# ad9200_breakout.net
KiCad netlist of a schematic drawn in EAGLE
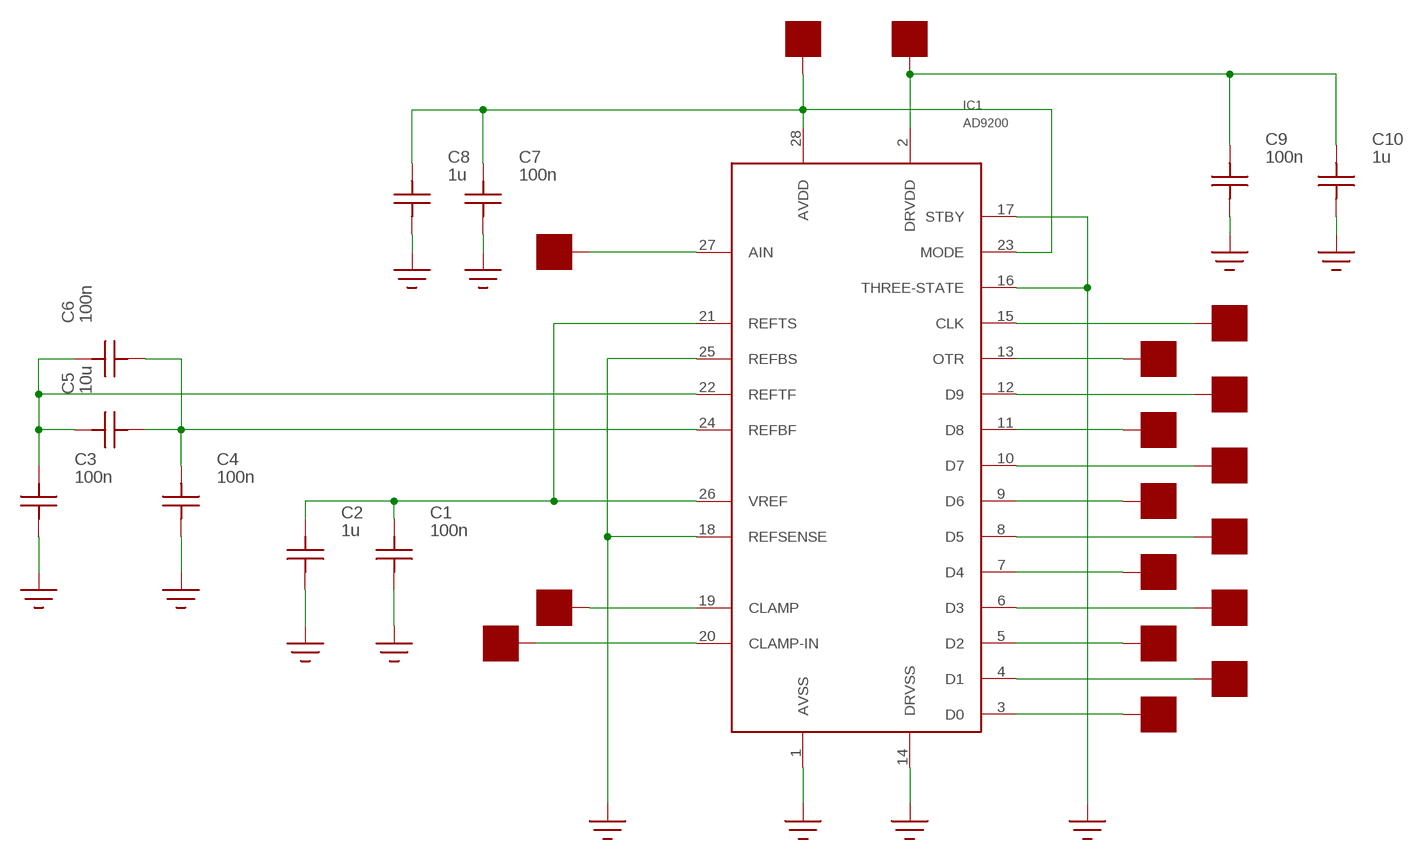
[diagram p0: schematic, sheet 1]

(export (version "E")
  (design (tool "Eeschema 10.0.6"))
  (components
    (comp (ref "C1")
      (value "100n")
      (footprint "eagle-import:C0603")
      (libsource (lib "eagle-import") (part "C0603"))
    )
    (comp (ref "C2")
      (value "1u")
      (footprint "eagle-import:C0603")
      (libsource (lib "eagle-import") (part "C0603"))
    )
    (comp (ref "C3")
      (value "100n")
      (footprint "eagle-import:C0603")
      (libsource (lib "eagle-import") (part "C0603"))
    )
    (comp (ref "C4")
      (value "100n")
      (footprint "eagle-import:C0603")
      (libsource (lib "eagle-import") (part "C0603"))
    )
    (comp (ref "C5")
      (value "10u")
      (footprint "eagle-import:C0603")
      (libsource (lib "eagle-import") (part "C0603"))
    )
    (comp (ref "C6")
      (value "100n")
      (footprint "eagle-import:C0603")
      (libsource (lib "eagle-import") (part "C0603"))
    )
    (comp (ref "C7")
      (value "100n")
      (footprint "eagle-import:C0603")
      (libsource (lib "eagle-import") (part "C0603"))
    )
    (comp (ref "C8")
      (value "1u")
      (footprint "eagle-import:C0603")
      (libsource (lib "eagle-import") (part "C0603"))
    )
    (comp (ref "C9")
      (value "100n")
      (footprint "eagle-import:C0603")
      (libsource (lib "eagle-import") (part "C0603"))
    )
    (comp (ref "C10")
      (value "1u")
      (footprint "eagle-import:C0603")
      (libsource (lib "eagle-import") (part "C0603"))
    )
    (comp (ref "IC1")
      (value "AD9200")
      (footprint "eagle-import:SSOP-28")
      (libsource (lib "eagle-import") (part "AD9200"))
    )
    (comp (ref "U$5")
      (value "PAD50MIL")
      (footprint "eagle-import:PAD_50MIL")
      (libsource (lib "eagle-import") (part "PAD50MIL"))
    )
    (comp (ref "U$6")
      (value "PAD50MIL")
      (footprint "eagle-import:PAD_50MIL")
      (libsource (lib "eagle-import") (part "PAD50MIL"))
    )
    (comp (ref "U$7")
      (value "PAD50MIL")
      (footprint "eagle-import:PAD_50MIL")
      (libsource (lib "eagle-import") (part "PAD50MIL"))
    )
    (comp (ref "U$8")
      (value "PAD50MIL")
      (footprint "eagle-import:PAD_50MIL")
      (libsource (lib "eagle-import") (part "PAD50MIL"))
    )
    (comp (ref "U$9")
      (value "PAD50MIL")
      (footprint "eagle-import:PAD_50MIL")
      (libsource (lib "eagle-import") (part "PAD50MIL"))
    )
    (comp (ref "U$10")
      (value "PAD50MIL")
      (footprint "eagle-import:PAD_50MIL")
      (libsource (lib "eagle-import") (part "PAD50MIL"))
    )
    (comp (ref "U$11")
      (value "PAD50MIL")
      (footprint "eagle-import:PAD_50MIL")
      (libsource (lib "eagle-import") (part "PAD50MIL"))
    )
    (comp (ref "U$12")
      (value "PAD50MIL")
      (footprint "eagle-import:PAD_50MIL")
      (libsource (lib "eagle-import") (part "PAD50MIL"))
    )
    (comp (ref "U$13")
      (value "PAD50MIL")
      (footprint "eagle-import:PAD_50MIL")
      (libsource (lib "eagle-import") (part "PAD50MIL"))
    )
    (comp (ref "U$14")
      (value "PAD50MIL")
      (footprint "eagle-import:PAD_50MIL")
      (libsource (lib "eagle-import") (part "PAD50MIL"))
    )
    (comp (ref "U$15")
      (value "PAD50MIL")
      (footprint "eagle-import:PAD_50MIL")
      (libsource (lib "eagle-import") (part "PAD50MIL"))
    )
    (comp (ref "U$16")
      (value "PAD50MIL")
      (footprint "eagle-import:PAD_50MIL")
      (libsource (lib "eagle-import") (part "PAD50MIL"))
    )
    (comp (ref "U$17")
      (value "PAD50MIL")
      (footprint "eagle-import:PAD_50MIL")
      (libsource (lib "eagle-import") (part "PAD50MIL"))
    )
    (comp (ref "U$18")
      (value "PAD50MIL")
      (footprint "eagle-import:PAD_50MIL")
      (libsource (lib "eagle-import") (part "PAD50MIL"))
    )
    (comp (ref "U$19")
      (value "PAD50MIL")
      (footprint "eagle-import:PAD_50MIL")
      (libsource (lib "eagle-import") (part "PAD50MIL"))
    )
    (comp (ref "U$20")
      (value "PAD50MIL")
      (footprint "eagle-import:PAD_50MIL")
      (libsource (lib "eagle-import") (part "PAD50MIL"))
    )
    (comp (ref "U$21")
      (value "PAD50MIL")
      (footprint "eagle-import:PAD_50MIL")
      (libsource (lib "eagle-import") (part "PAD50MIL"))
    )
  )
  (nets
    (net (code "1") (name "GND") (class "Default")
      (node (ref "C1") (pin "P$1") (pinfunction "P$1_P$1") (pintype "bidirectional"))
      (node (ref "C10") (pin "P$1") (pinfunction "P$1_P$1") (pintype "bidirectional"))
      (node (ref "C2") (pin "P$1") (pinfunction "P$1_P$1") (pintype "bidirectional"))
      (node (ref "C3") (pin "P$1") (pinfunction "P$1_P$1") (pintype "bidirectional"))
      (node (ref "C4") (pin "P$1") (pinfunction "P$1_P$1") (pintype "bidirectional"))
      (node (ref "C7") (pin "P$1") (pinfunction "P$1_P$1") (pintype "bidirectional"))
      (node (ref "C8") (pin "P$1") (pinfunction "P$1_P$1") (pintype "bidirectional"))
      (node (ref "C9") (pin "P$1") (pinfunction "P$1_P$1") (pintype "bidirectional"))
      (node (ref "IC1") (pin "1") (pinfunction "AVSS_1") (pintype "bidirectional"))
      (node (ref "IC1") (pin "14") (pinfunction "DRVSS_14") (pintype "bidirectional"))
      (node (ref "IC1") (pin "16") (pinfunction "THREE-STATE_16") (pintype "bidirectional"))
      (node (ref "IC1") (pin "17") (pinfunction "STBY_17") (pintype "bidirectional"))
      (node (ref "IC1") (pin "18") (pinfunction "REFSENSE_18") (pintype "bidirectional"))
      (node (ref "IC1") (pin "25") (pinfunction "REFBS_25") (pintype "bidirectional"))
    )
    (net (code "2") (name "Net-(IC1-AIN)") (class "Default")
      (node (ref "IC1") (pin "27") (pinfunction "AIN_27") (pintype "bidirectional"))
      (node (ref "U$17") (pin "P$1") (pinfunction "P$1_P$1") (pintype "bidirectional"))
    )
    (net (code "3") (name "Net-(IC1-AVDD)") (class "Default")
      (node (ref "C7") (pin "P$2") (pinfunction "P$2_P$2") (pintype "bidirectional"))
      (node (ref "C8") (pin "P$2") (pinfunction "P$2_P$2") (pintype "bidirectional"))
      (node (ref "IC1") (pin "23") (pinfunction "MODE_23") (pintype "bidirectional"))
      (node (ref "IC1") (pin "28") (pinfunction "AVDD_28") (pintype "bidirectional"))
      (node (ref "U$18") (pin "P$1") (pinfunction "P$1_P$1") (pintype "bidirectional"))
    )
    (net (code "4") (name "Net-(IC1-CLAMP)") (class "Default")
      (node (ref "IC1") (pin "19") (pinfunction "CLAMP_19") (pintype "bidirectional"))
      (node (ref "U$20") (pin "P$1") (pinfunction "P$1_P$1") (pintype "bidirectional"))
    )
    (net (code "5") (name "Net-(IC1-CLAMP-IN)") (class "Default")
      (node (ref "IC1") (pin "20") (pinfunction "CLAMP-IN_20") (pintype "bidirectional"))
      (node (ref "U$21") (pin "P$1") (pinfunction "P$1_P$1") (pintype "bidirectional"))
    )
    (net (code "6") (name "Net-(IC1-CLK)") (class "Default")
      (node (ref "IC1") (pin "15") (pinfunction "CLK_15") (pintype "bidirectional"))
      (node (ref "U$16") (pin "P$1") (pinfunction "P$1_P$1") (pintype "bidirectional"))
    )
    (net (code "7") (name "Net-(IC1-D0)") (class "Default")
      (node (ref "IC1") (pin "3") (pinfunction "D0_3") (pintype "bidirectional"))
      (node (ref "U$5") (pin "P$1") (pinfunction "P$1_P$1") (pintype "bidirectional"))
    )
    (net (code "8") (name "Net-(IC1-D1)") (class "Default")
      (node (ref "IC1") (pin "4") (pinfunction "D1_4") (pintype "bidirectional"))
      (node (ref "U$6") (pin "P$1") (pinfunction "P$1_P$1") (pintype "bidirectional"))
    )
    (net (code "9") (name "Net-(IC1-D2)") (class "Default")
      (node (ref "IC1") (pin "5") (pinfunction "D2_5") (pintype "bidirectional"))
      (node (ref "U$7") (pin "P$1") (pinfunction "P$1_P$1") (pintype "bidirectional"))
    )
    (net (code "10") (name "Net-(IC1-D3)") (class "Default")
      (node (ref "IC1") (pin "6") (pinfunction "D3_6") (pintype "bidirectional"))
      (node (ref "U$8") (pin "P$1") (pinfunction "P$1_P$1") (pintype "bidirectional"))
    )
    (net (code "11") (name "Net-(IC1-D4)") (class "Default")
      (node (ref "IC1") (pin "7") (pinfunction "D4_7") (pintype "bidirectional"))
      (node (ref "U$9") (pin "P$1") (pinfunction "P$1_P$1") (pintype "bidirectional"))
    )
    (net (code "12") (name "Net-(IC1-D5)") (class "Default")
      (node (ref "IC1") (pin "8") (pinfunction "D5_8") (pintype "bidirectional"))
      (node (ref "U$10") (pin "P$1") (pinfunction "P$1_P$1") (pintype "bidirectional"))
    )
    (net (code "13") (name "Net-(IC1-D6)") (class "Default")
      (node (ref "IC1") (pin "9") (pinfunction "D6_9") (pintype "bidirectional"))
      (node (ref "U$11") (pin "P$1") (pinfunction "P$1_P$1") (pintype "bidirectional"))
    )
    (net (code "14") (name "Net-(IC1-D7)") (class "Default")
      (node (ref "IC1") (pin "10") (pinfunction "D7_10") (pintype "bidirectional"))
      (node (ref "U$12") (pin "P$1") (pinfunction "P$1_P$1") (pintype "bidirectional"))
    )
    (net (code "15") (name "Net-(IC1-D8)") (class "Default")
      (node (ref "IC1") (pin "11") (pinfunction "D8_11") (pintype "bidirectional"))
      (node (ref "U$13") (pin "P$1") (pinfunction "P$1_P$1") (pintype "bidirectional"))
    )
    (net (code "16") (name "Net-(IC1-D9)") (class "Default")
      (node (ref "IC1") (pin "12") (pinfunction "D9_12") (pintype "bidirectional"))
      (node (ref "U$14") (pin "P$1") (pinfunction "P$1_P$1") (pintype "bidirectional"))
    )
    (net (code "17") (name "Net-(IC1-DRVDD)") (class "Default")
      (node (ref "C10") (pin "P$2") (pinfunction "P$2_P$2") (pintype "bidirectional"))
      (node (ref "C9") (pin "P$2") (pinfunction "P$2_P$2") (pintype "bidirectional"))
      (node (ref "IC1") (pin "2") (pinfunction "DRVDD_2") (pintype "bidirectional"))
      (node (ref "U$19") (pin "P$1") (pinfunction "P$1_P$1") (pintype "bidirectional"))
    )
    (net (code "18") (name "Net-(IC1-OTR)") (class "Default")
      (node (ref "IC1") (pin "13") (pinfunction "OTR_13") (pintype "bidirectional"))
      (node (ref "U$15") (pin "P$1") (pinfunction "P$1_P$1") (pintype "bidirectional"))
    )
    (net (code "19") (name "Net-(IC1-REFBF)") (class "Default")
      (node (ref "C4") (pin "P$2") (pinfunction "P$2_P$2") (pintype "bidirectional"))
      (node (ref "C5") (pin "P$1") (pinfunction "P$1_P$1") (pintype "bidirectional"))
      (node (ref "C6") (pin "P$1") (pinfunction "P$1_P$1") (pintype "bidirectional"))
      (node (ref "IC1") (pin "24") (pinfunction "REFBF_24") (pintype "bidirectional"))
    )
    (net (code "20") (name "Net-(IC1-REFTF)") (class "Default")
      (node (ref "C3") (pin "P$2") (pinfunction "P$2_P$2") (pintype "bidirectional"))
      (node (ref "C5") (pin "P$2") (pinfunction "P$2_P$2") (pintype "bidirectional"))
      (node (ref "C6") (pin "P$2") (pinfunction "P$2_P$2") (pintype "bidirectional"))
      (node (ref "IC1") (pin "22") (pinfunction "REFTF_22") (pintype "bidirectional"))
    )
    (net (code "21") (name "Net-(IC1-REFTS)") (class "Default")
      (node (ref "C1") (pin "P$2") (pinfunction "P$2_P$2") (pintype "bidirectional"))
      (node (ref "C2") (pin "P$2") (pinfunction "P$2_P$2") (pintype "bidirectional"))
      (node (ref "IC1") (pin "21") (pinfunction "REFTS_21") (pintype "bidirectional"))
      (node (ref "IC1") (pin "26") (pinfunction "VREF_26") (pintype "bidirectional"))
    )
  )
)
